# telecommande.net
KiCad netlist of a schematic drawn in EAGLE
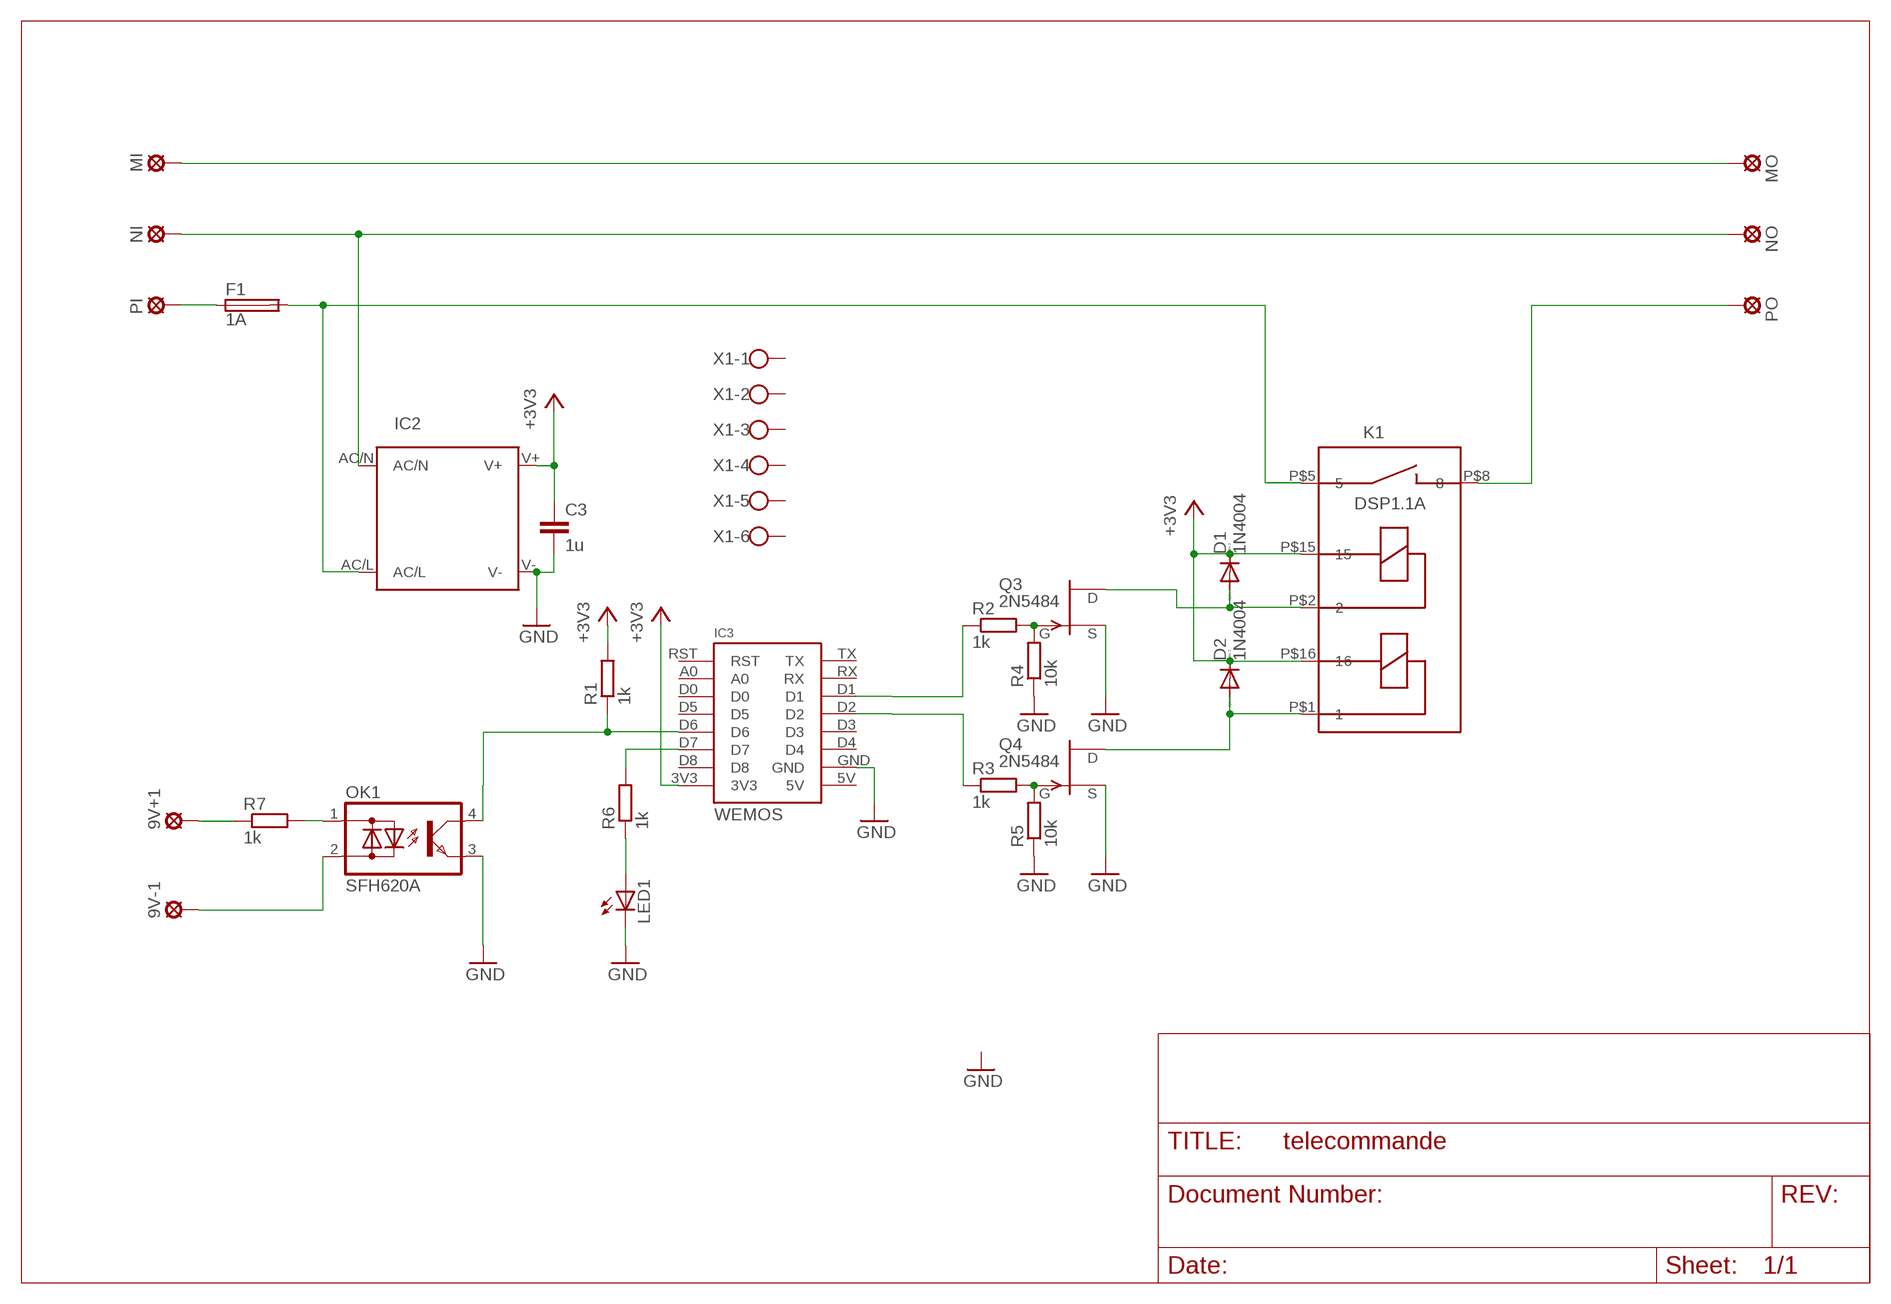
[diagram p0: schematic, sheet 1]

(export (version "E")
  (design (tool "Eeschema 10.0.6"))
  (components
    (comp (ref "9V+1")
      (value "LSP13")
      (footprint "eagle-import:LSP13")
      (libsource (lib "eagle-import") (part "LSP13"))
    )
    (comp (ref "9V-1")
      (value "LSP13")
      (footprint "eagle-import:LSP13")
      (libsource (lib "eagle-import") (part "LSP13"))
    )
    (comp (ref "C3")
      (value "1u")
      (footprint "eagle-import:C025-024X044")
      (libsource (lib "eagle-import") (part "C-EU025-024X044"))
    )
    (comp (ref "D1")
      (value "1N4004")
      (footprint "eagle-import:DO41-10")
      (libsource (lib "eagle-import") (part "1N4004"))
    )
    (comp (ref "D2")
      (value "1N4004")
      (footprint "eagle-import:DO41-10")
      (libsource (lib "eagle-import") (part "1N4004"))
    )
    (comp (ref "F1")
      (value "1A")
      (footprint "eagle-import:GSH15")
      (fields (field (name "MPN") "64900001039"))
      (libsource (lib "eagle-import") (part "GSH15"))
    )
    (comp (ref "IC2")
      (value "IRM_03")
      (footprint "eagle-import:IRM_03")
      (libsource (lib "eagle-import") (part "IRM_03"))
    )
    (comp (ref "IC3")
      (value "WEMOS")
      (footprint "eagle-import:WEMOS")
      (libsource (lib "eagle-import") (part "WEMOS"))
    )
    (comp (ref "K1")
      (value "DSP1.1A")
      (footprint "eagle-import:DSP1A")
      (libsource (lib "eagle-import") (part "DSP1.1A"))
    )
    (comp (ref "LED1")
      (value "LED3MM")
      (footprint "eagle-import:LED3MM")
      (libsource (lib "eagle-import") (part "LED3MM"))
    )
    (comp (ref "MI")
      (value "LSP13")
      (footprint "eagle-import:LSP13")
      (libsource (lib "eagle-import") (part "LSP13"))
    )
    (comp (ref "MO")
      (value "LSP13")
      (footprint "eagle-import:LSP13")
      (libsource (lib "eagle-import") (part "LSP13"))
    )
    (comp (ref "NI")
      (value "LSP13")
      (footprint "eagle-import:LSP13")
      (libsource (lib "eagle-import") (part "LSP13"))
    )
    (comp (ref "NO")
      (value "LSP13")
      (footprint "eagle-import:LSP13")
      (libsource (lib "eagle-import") (part "LSP13"))
    )
    (comp (ref "OK1")
      (value "SFH620A")
      (footprint "eagle-import:DIL04")
      (fields (field (name "MPN") "SFH620A-2"))
      (libsource (lib "eagle-import") (part "SFH620A"))
    )
    (comp (ref "PI")
      (value "LSP13")
      (footprint "eagle-import:LSP13")
      (libsource (lib "eagle-import") (part "LSP13"))
    )
    (comp (ref "PO")
      (value "LSP13")
      (footprint "eagle-import:LSP13")
      (libsource (lib "eagle-import") (part "LSP13"))
    )
    (comp (ref "Q3")
      (value "2N5484")
      (footprint "eagle-import:TO92-")
      (libsource (lib "eagle-import") (part "?5482N4"))
    )
    (comp (ref "Q4")
      (value "2N5484")
      (footprint "eagle-import:TO92-")
      (libsource (lib "eagle-import") (part "?5482N4"))
    )
    (comp (ref "R1")
      (value "1k")
      (footprint "eagle-import:0207_10")
      (libsource (lib "eagle-import") (part "R-EU_0207/10"))
    )
    (comp (ref "R2")
      (value "1k")
      (footprint "eagle-import:0207_10")
      (libsource (lib "eagle-import") (part "R-EU_0207/10"))
    )
    (comp (ref "R3")
      (value "1k")
      (footprint "eagle-import:0207_10")
      (libsource (lib "eagle-import") (part "R-EU_0207/10"))
    )
    (comp (ref "R4")
      (value "10k")
      (footprint "eagle-import:0207_10")
      (libsource (lib "eagle-import") (part "R-EU_0207/10"))
    )
    (comp (ref "R5")
      (value "10k")
      (footprint "eagle-import:0207_10")
      (libsource (lib "eagle-import") (part "R-EU_0207/10"))
    )
    (comp (ref "R6")
      (value "1k")
      (footprint "eagle-import:0207_10")
      (libsource (lib "eagle-import") (part "R-EU_0207/10"))
    )
    (comp (ref "R7")
      (value "1k")
      (footprint "eagle-import:0207_10")
      (libsource (lib "eagle-import") (part "R-EU_0207/10"))
    )
    (comp (ref "X1")
      (value "W237-6")
      (footprint "eagle-import:W237-6")
      (libsource (lib "eagle-import") (part "W237-6"))
    )
  )
  (nets
    (net (code "1") (name "+3V3") (class "Default")
      (node (ref "C3") (pin "1") (pinfunction "1_1") (pintype "passive"))
      (node (ref "D1") (pin "C") (pinfunction "C_C") (pintype "passive"))
      (node (ref "D2") (pin "C") (pinfunction "C_C") (pintype "passive"))
      (node (ref "IC2") (pin "V+") (pinfunction "V+_V+") (pintype "output"))
      (node (ref "IC3") (pin "3V3") (pinfunction "3V3_3V3") (pintype "bidirectional"))
      (node (ref "K1") (pin "P$15") (pinfunction "15_P$15") (pintype "bidirectional"))
      (node (ref "K1") (pin "P$16") (pinfunction "16_P$16") (pintype "bidirectional"))
      (node (ref "R1") (pin "2") (pinfunction "2_2") (pintype "passive"))
    )
    (net (code "2") (name "GND") (class "Default")
      (node (ref "C3") (pin "2") (pinfunction "2_2") (pintype "passive"))
      (node (ref "IC2") (pin "V-") (pinfunction "V-_V-") (pintype "output"))
      (node (ref "IC3") (pin "GND") (pinfunction "GND_GND") (pintype "bidirectional"))
      (node (ref "LED1") (pin "K") (pinfunction "C_K") (pintype "passive"))
      (node (ref "OK1") (pin "3") (pinfunction "E_3") (pintype "passive"))
      (node (ref "Q3") (pin "2") (pinfunction "S_2") (pintype "passive"))
      (node (ref "Q4") (pin "2") (pinfunction "S_2") (pintype "passive"))
      (node (ref "R4") (pin "1") (pinfunction "1_1") (pintype "passive"))
      (node (ref "R5") (pin "1") (pinfunction "1_1") (pintype "passive"))
    )
    (net (code "3") (name "Net-(9V+1-PadMP)") (class "Default")
      (node (ref "9V+1") (pin "MP") (pinfunction "MP_MP") (pintype "passive"))
      (node (ref "R7") (pin "1") (pinfunction "1_1") (pintype "passive"))
    )
    (net (code "4") (name "Net-(F1-Pad1)") (class "Default")
      (node (ref "F1") (pin "1") (pinfunction "1_1") (pintype "passive"))
      (node (ref "PI") (pin "MP") (pinfunction "MP_MP") (pintype "passive"))
    )
    (net (code "5") (name "Net-(IC2-PadAC{slash}N)") (class "Default")
      (node (ref "IC2") (pin "AC/N") (pinfunction "AC/N_AC/N") (pintype "input"))
      (node (ref "NI") (pin "MP") (pinfunction "MP_MP") (pintype "passive"))
      (node (ref "NO") (pin "MP") (pinfunction "MP_MP") (pintype "passive"))
    )
    (net (code "6") (name "Net-(IC3-PadD1)") (class "Default")
      (node (ref "IC3") (pin "D1") (pinfunction "D1_D1") (pintype "bidirectional"))
      (node (ref "R2") (pin "1") (pinfunction "1_1") (pintype "passive"))
    )
    (net (code "7") (name "Net-(IC3-PadD2)") (class "Default")
      (node (ref "IC3") (pin "D2") (pinfunction "D2_D2") (pintype "bidirectional"))
      (node (ref "R3") (pin "1") (pinfunction "1_1") (pintype "passive"))
    )
    (net (code "8") (name "Net-(IC3-PadD7)") (class "Default")
      (node (ref "IC3") (pin "D7") (pinfunction "D7_D7") (pintype "bidirectional"))
      (node (ref "R6") (pin "2") (pinfunction "2_2") (pintype "passive"))
    )
    (net (code "9") (name "Net-(K1-1)") (class "Default")
      (node (ref "D2") (pin "A") (pinfunction "A_A") (pintype "passive"))
      (node (ref "K1") (pin "P$1") (pinfunction "1_P$1") (pintype "bidirectional"))
      (node (ref "Q4") (pin "3") (pinfunction "D_3") (pintype "passive"))
    )
    (net (code "10") (name "Net-(K1-2)") (class "Default")
      (node (ref "D1") (pin "A") (pinfunction "A_A") (pintype "passive"))
      (node (ref "K1") (pin "P$2") (pinfunction "2_P$2") (pintype "bidirectional"))
      (node (ref "Q3") (pin "3") (pinfunction "D_3") (pintype "passive"))
    )
    (net (code "11") (name "Net-(K1-5)") (class "Default")
      (node (ref "F1") (pin "2") (pinfunction "2_2") (pintype "passive"))
      (node (ref "IC2") (pin "AC/L") (pinfunction "AC/L_AC/L") (pintype "input"))
      (node (ref "K1") (pin "P$5") (pinfunction "5_P$5") (pintype "bidirectional"))
    )
    (net (code "12") (name "Net-(K1-8)") (class "Default")
      (node (ref "K1") (pin "P$8") (pinfunction "8_P$8") (pintype "bidirectional"))
      (node (ref "PO") (pin "MP") (pinfunction "MP_MP") (pintype "passive"))
    )
    (net (code "13") (name "Net-(LED1-PadA)") (class "Default")
      (node (ref "LED1") (pin "A") (pinfunction "A_A") (pintype "passive"))
      (node (ref "R6") (pin "1") (pinfunction "1_1") (pintype "passive"))
    )
    (net (code "14") (name "Net-(MI-PadMP)") (class "Default")
      (node (ref "MI") (pin "MP") (pinfunction "MP_MP") (pintype "passive"))
      (node (ref "MO") (pin "MP") (pinfunction "MP_MP") (pintype "passive"))
    )
    (net (code "15") (name "Net-(OK1-AC1)") (class "Default")
      (node (ref "OK1") (pin "1") (pinfunction "AC1_1") (pintype "passive"))
      (node (ref "R7") (pin "2") (pinfunction "2_2") (pintype "passive"))
    )
    (net (code "16") (name "Net-(OK1-AC2)") (class "Default")
      (node (ref "9V-1") (pin "MP") (pinfunction "MP_MP") (pintype "passive"))
      (node (ref "OK1") (pin "2") (pinfunction "AC2_2") (pintype "passive"))
    )
    (net (code "17") (name "Net-(OK1-C)") (class "Default")
      (node (ref "IC3") (pin "D6") (pinfunction "D6_D6") (pintype "bidirectional"))
      (node (ref "OK1") (pin "4") (pinfunction "C_4") (pintype "passive"))
      (node (ref "R1") (pin "1") (pinfunction "1_1") (pintype "passive"))
    )
    (net (code "18") (name "Net-(Q3-G)") (class "Default")
      (node (ref "Q3") (pin "1") (pinfunction "G_1") (pintype "passive"))
      (node (ref "R2") (pin "2") (pinfunction "2_2") (pintype "passive"))
      (node (ref "R4") (pin "2") (pinfunction "2_2") (pintype "passive"))
    )
    (net (code "19") (name "Net-(Q4-G)") (class "Default")
      (node (ref "Q4") (pin "1") (pinfunction "G_1") (pintype "passive"))
      (node (ref "R3") (pin "2") (pinfunction "2_2") (pintype "passive"))
      (node (ref "R5") (pin "2") (pinfunction "2_2") (pintype "passive"))
    )
    (net (code "20") (name "unconnected-(IC3-Pad5V)") (class "Default")
      (node (ref "IC3") (pin "5V") (pinfunction "5V_5V") (pintype "bidirectional"))
    )
    (net (code "21") (name "unconnected-(IC3-PadA0)") (class "Default")
      (node (ref "IC3") (pin "A0") (pinfunction "A0_A0") (pintype "bidirectional"))
    )
    (net (code "22") (name "unconnected-(IC3-PadD0)") (class "Default")
      (node (ref "IC3") (pin "D0") (pinfunction "D0_D0") (pintype "bidirectional"))
    )
    (net (code "23") (name "unconnected-(IC3-PadD3)") (class "Default")
      (node (ref "IC3") (pin "D3") (pinfunction "D3_D3") (pintype "bidirectional"))
    )
    (net (code "24") (name "unconnected-(IC3-PadD4)") (class "Default")
      (node (ref "IC3") (pin "D4") (pinfunction "D4_D4") (pintype "bidirectional"))
    )
    (net (code "25") (name "unconnected-(IC3-PadD5)") (class "Default")
      (node (ref "IC3") (pin "D5") (pinfunction "D5_D5") (pintype "bidirectional"))
    )
    (net (code "26") (name "unconnected-(IC3-PadD8)") (class "Default")
      (node (ref "IC3") (pin "D8") (pinfunction "D8_D8") (pintype "bidirectional"))
    )
    (net (code "27") (name "unconnected-(IC3-PadRST)") (class "Default")
      (node (ref "IC3") (pin "RST") (pinfunction "RST_RST") (pintype "bidirectional"))
    )
    (net (code "28") (name "unconnected-(IC3-PadRX)") (class "Default")
      (node (ref "IC3") (pin "RX") (pinfunction "RX_RX") (pintype "bidirectional"))
    )
    (net (code "29") (name "unconnected-(IC3-PadTX)") (class "Default")
      (node (ref "IC3") (pin "TX") (pinfunction "TX_TX") (pintype "bidirectional"))
    )
    (net (code "30") (name "unconnected-(X1A-KL-Pad1)") (class "Default")
      (node (ref "X1") (pin "1") (pinfunction "KL_1") (pintype "passive"))
    )
    (net (code "31") (name "unconnected-(X1B-KL-Pad2)") (class "Default")
      (node (ref "X1") (pin "2") (pinfunction "KL_2") (pintype "passive"))
    )
    (net (code "32") (name "unconnected-(X1C-KL-Pad3)") (class "Default")
      (node (ref "X1") (pin "3") (pinfunction "KL_3") (pintype "passive"))
    )
    (net (code "33") (name "unconnected-(X1D-KL-Pad4)") (class "Default")
      (node (ref "X1") (pin "4") (pinfunction "KL_4") (pintype "passive"))
    )
    (net (code "34") (name "unconnected-(X1E-KL-Pad5)") (class "Default")
      (node (ref "X1") (pin "5") (pinfunction "KL_5") (pintype "passive"))
    )
    (net (code "35") (name "unconnected-(X1F-KL-Pad6)") (class "Default")
      (node (ref "X1") (pin "6") (pinfunction "KL_6") (pintype "passive"))
    )
  )
)
